# SparkFun_DataLogger_IoT.net
KiCad netlist of a schematic drawn in EAGLE
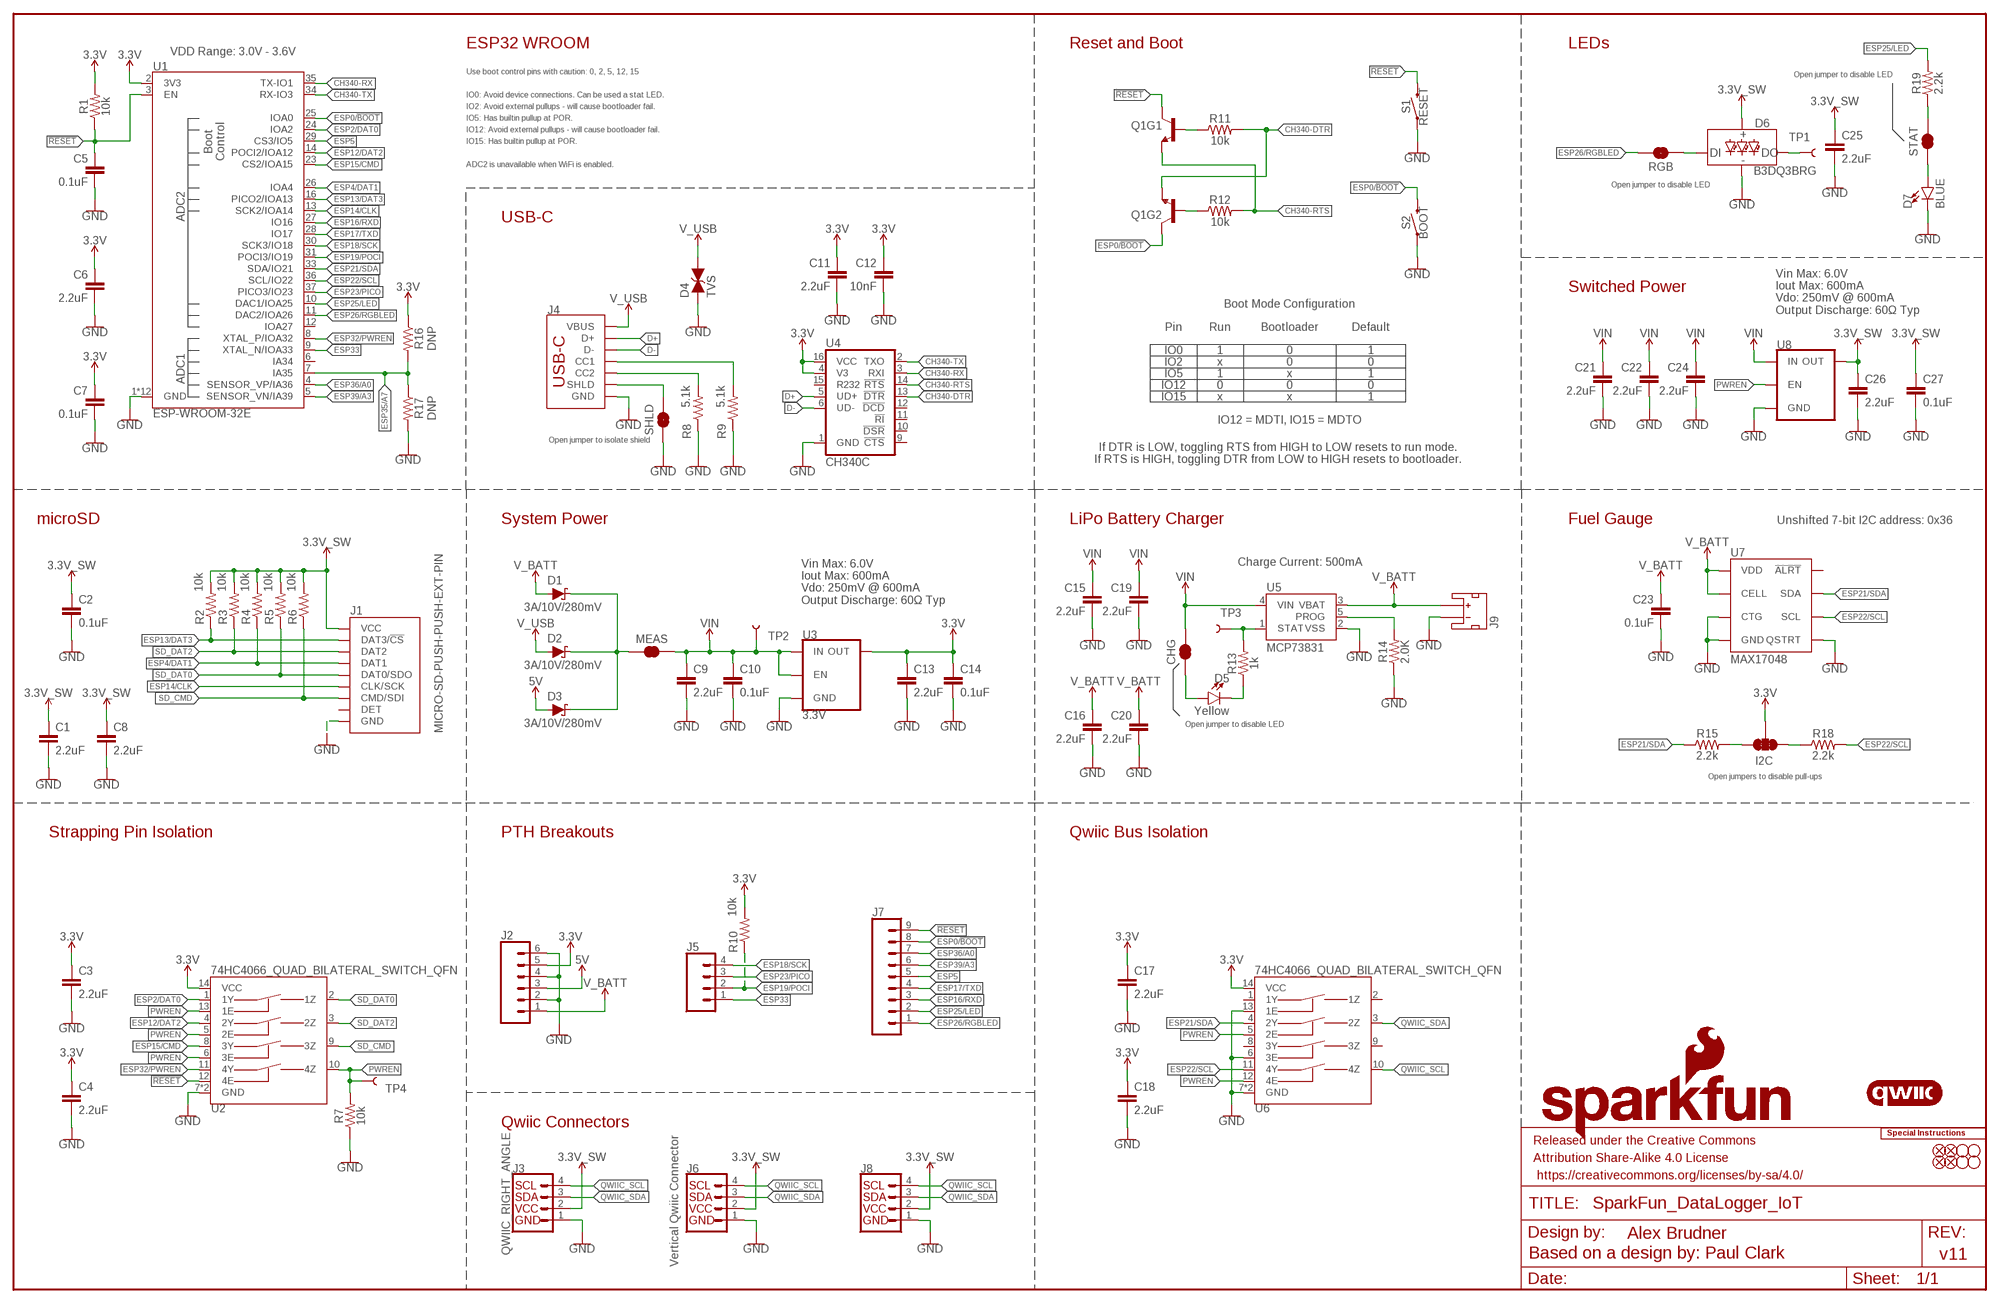
[diagram p0: schematic, sheet 1]

(export (version "E")
  (design (tool "Eeschema 10.0.6"))
  (components
    (comp (ref "C1")
      (value "2.2uF")
      (footprint "eagle-import:0402-TIGHT")
      (libsource (lib "eagle-import") (part "2.2UF-0402_TIGHT-10V-10%-X5R"))
    )
    (comp (ref "C2")
      (value "0.1uF")
      (footprint "eagle-import:0402-TIGHT")
      (libsource (lib "eagle-import") (part "0.1UF-0402T-6.3V-10%-X7R"))
    )
    (comp (ref "C3")
      (value "2.2uF")
      (footprint "eagle-import:0402-TIGHT")
      (libsource (lib "eagle-import") (part "2.2UF-0402_TIGHT-10V-10%-X5R"))
    )
    (comp (ref "C4")
      (value "2.2uF")
      (footprint "eagle-import:0402-TIGHT")
      (libsource (lib "eagle-import") (part "2.2UF-0402_TIGHT-10V-10%-X5R"))
    )
    (comp (ref "C5")
      (value "0.1uF")
      (footprint "eagle-import:0402-TIGHT")
      (libsource (lib "eagle-import") (part "0.1UF-0402T-6.3V-10%-X7R"))
    )
    (comp (ref "C6")
      (value "2.2uF")
      (footprint "eagle-import:0402-TIGHT")
      (libsource (lib "eagle-import") (part "2.2UF-0402_TIGHT-10V-10%-X5R"))
    )
    (comp (ref "C7")
      (value "0.1uF")
      (footprint "eagle-import:0402-TIGHT")
      (libsource (lib "eagle-import") (part "0.1UF-0402T-6.3V-10%-X7R"))
    )
    (comp (ref "C8")
      (value "2.2uF")
      (footprint "eagle-import:0402-TIGHT")
      (libsource (lib "eagle-import") (part "2.2UF-0402_TIGHT-10V-10%-X5R"))
    )
    (comp (ref "C9")
      (value "2.2uF")
      (footprint "eagle-import:0402-TIGHT")
      (libsource (lib "eagle-import") (part "2.2UF-0402_TIGHT-10V-10%-X5R"))
    )
    (comp (ref "C10")
      (value "0.1uF")
      (footprint "eagle-import:0402-TIGHT")
      (libsource (lib "eagle-import") (part "0.1UF-0402T-6.3V-10%-X7R"))
    )
    (comp (ref "C11")
      (value "2.2uF")
      (footprint "eagle-import:0402-TIGHT")
      (libsource (lib "eagle-import") (part "2.2UF-0402_TIGHT-10V-10%-X5R"))
    )
    (comp (ref "C12")
      (value "10nF")
      (footprint "eagle-import:0402-TIGHT")
      (libsource (lib "eagle-import") (part "10NF-0402T-25V-10%-X7R-WE"))
    )
    (comp (ref "C13")
      (value "2.2uF")
      (footprint "eagle-import:0402-TIGHT")
      (libsource (lib "eagle-import") (part "2.2UF-0402_TIGHT-10V-10%-X5R"))
    )
    (comp (ref "C14")
      (value "0.1uF")
      (footprint "eagle-import:0402-TIGHT")
      (libsource (lib "eagle-import") (part "0.1UF-0402T-6.3V-10%-X7R"))
    )
    (comp (ref "C15")
      (value "2.2uF")
      (footprint "eagle-import:0402-TIGHT")
      (libsource (lib "eagle-import") (part "2.2UF-0402_TIGHT-10V-10%-X5R"))
    )
    (comp (ref "C16")
      (value "2.2uF")
      (footprint "eagle-import:0402-TIGHT")
      (libsource (lib "eagle-import") (part "2.2UF-0402_TIGHT-10V-10%-X5R"))
    )
    (comp (ref "C17")
      (value "2.2uF")
      (footprint "eagle-import:0402-TIGHT")
      (libsource (lib "eagle-import") (part "2.2UF-0402_TIGHT-10V-10%-X5R"))
    )
    (comp (ref "C18")
      (value "2.2uF")
      (footprint "eagle-import:0402-TIGHT")
      (libsource (lib "eagle-import") (part "2.2UF-0402_TIGHT-10V-10%-X5R"))
    )
    (comp (ref "C19")
      (value "2.2uF")
      (footprint "eagle-import:0402-TIGHT")
      (libsource (lib "eagle-import") (part "2.2UF-0402_TIGHT-10V-10%-X5R"))
    )
    (comp (ref "C20")
      (value "2.2uF")
      (footprint "eagle-import:0402-TIGHT")
      (libsource (lib "eagle-import") (part "2.2UF-0402_TIGHT-10V-10%-X5R"))
    )
    (comp (ref "C21")
      (value "2.2uF")
      (footprint "eagle-import:0402-TIGHT")
      (libsource (lib "eagle-import") (part "2.2UF-0402_TIGHT-10V-10%-X5R"))
    )
    (comp (ref "C22")
      (value "2.2uF")
      (footprint "eagle-import:0402-TIGHT")
      (libsource (lib "eagle-import") (part "2.2UF-0402_TIGHT-10V-10%-X5R"))
    )
    (comp (ref "C23")
      (value "0.1uF")
      (footprint "eagle-import:0402-TIGHT")
      (libsource (lib "eagle-import") (part "0.1UF-0402T-6.3V-10%-X7R"))
    )
    (comp (ref "C24")
      (value "2.2uF")
      (footprint "eagle-import:0402-TIGHT")
      (libsource (lib "eagle-import") (part "2.2UF-0402_TIGHT-10V-10%-X5R"))
    )
    (comp (ref "C25")
      (value "2.2uF")
      (footprint "eagle-import:0402-TIGHT")
      (libsource (lib "eagle-import") (part "2.2UF-0402_TIGHT-10V-10%-X5R"))
    )
    (comp (ref "C26")
      (value "2.2uF")
      (footprint "eagle-import:0402-TIGHT")
      (libsource (lib "eagle-import") (part "2.2UF-0402_TIGHT-10V-10%-X5R"))
    )
    (comp (ref "C27")
      (value "0.1uF")
      (footprint "eagle-import:0402-TIGHT")
      (libsource (lib "eagle-import") (part "0.1UF-0402T-6.3V-10%-X7R"))
    )
    (comp (ref "CHG")
      (value "JUMPER-SMT_2_NC_TRACE_SILK")
      (footprint "eagle-import:SMT-JUMPER_2_NC_TRACE_SILK")
      (libsource (lib "eagle-import") (part "JUMPER-SMT_2_NC_TRACE_SILK"))
    )
    (comp (ref "D1")
      (value "3A/10V/280mV")
      (footprint "eagle-import:SOD-323")
      (libsource (lib "eagle-import") (part "DIODE-SCHOTTKY-BAT60A"))
    )
    (comp (ref "D2")
      (value "3A/10V/280mV")
      (footprint "eagle-import:SOD-323")
      (libsource (lib "eagle-import") (part "DIODE-SCHOTTKY-BAT60A"))
    )
    (comp (ref "D3")
      (value "3A/10V/280mV")
      (footprint "eagle-import:SOD-323")
      (libsource (lib "eagle-import") (part "DIODE-SCHOTTKY-BAT60A"))
    )
    (comp (ref "D4")
      (value "TVS")
      (footprint "eagle-import:0603")
      (libsource (lib "eagle-import") (part "DIODE_TVS"))
    )
    (comp (ref "D5")
      (value "Yellow")
      (footprint "eagle-import:LED-0603")
      (libsource (lib "eagle-import") (part "LED-YELLOW0603"))
    )
    (comp (ref "D6")
      (value "B3DQ3BRG")
      (footprint "eagle-import:B3DQ3BRG")
      (libsource (lib "eagle-import") (part "B3DQ3BRG"))
    )
    (comp (ref "D7")
      (value "BLUE")
      (footprint "eagle-import:LED-0603")
      (libsource (lib "eagle-import") (part "LED-BLUE0603"))
    )
    (comp (ref "FD1")
      (value "FIDUCIAL1X2")
      (footprint "eagle-import:FIDUCIAL-1X2")
      (libsource (lib "eagle-import") (part "FIDUCIAL1X2"))
    )
    (comp (ref "FD2")
      (value "FIDUCIAL1X2")
      (footprint "eagle-import:FIDUCIAL-1X2")
      (libsource (lib "eagle-import") (part "FIDUCIAL1X2"))
    )
    (comp (ref "FD3")
      (value "FIDUCIAL1X2")
      (footprint "eagle-import:FIDUCIAL-1X2")
      (libsource (lib "eagle-import") (part "FIDUCIAL1X2"))
    )
    (comp (ref "FD4")
      (value "FIDUCIAL1X2")
      (footprint "eagle-import:FIDUCIAL-1X2")
      (libsource (lib "eagle-import") (part "FIDUCIAL1X2"))
    )
    (comp (ref "FRAME1")
      (value "FRAME-LEDGER")
      (footprint "eagle-import:CREATIVE_COMMONS")
      (fields (field (name "DESIGNER") "Alex Brudner") (field (name "REV") "v11"))
      (libsource (lib "eagle-import") (part "FRAME-LEDGER"))
    )
    (comp (ref "H1")
      (value "STAND-OFFTIGHT")
      (footprint "eagle-import:STAND-OFF-TIGHT")
      (libsource (lib "eagle-import") (part "STAND-OFFTIGHT"))
    )
    (comp (ref "H2")
      (value "STAND-OFFTIGHT")
      (footprint "eagle-import:STAND-OFF-TIGHT")
      (libsource (lib "eagle-import") (part "STAND-OFFTIGHT"))
    )
    (comp (ref "H3")
      (value "STAND-OFFTIGHT")
      (footprint "eagle-import:STAND-OFF-TIGHT")
      (libsource (lib "eagle-import") (part "STAND-OFFTIGHT"))
    )
    (comp (ref "H4")
      (value "STAND-OFFTIGHT")
      (footprint "eagle-import:STAND-OFF-TIGHT")
      (libsource (lib "eagle-import") (part "STAND-OFFTIGHT"))
    )
    (comp (ref "I2C")
      (value "JUMPER-SMT_3_2-NC_TRACE_SILK")
      (footprint "eagle-import:SMT-JUMPER_3_2-NC_TRACE_SILK")
      (libsource (lib "eagle-import") (part "JUMPER-SMT_3_2-NC_TRACE_SILK"))
    )
    (comp (ref "J1")
      (value "MICRO-SD-PUSH-PUSH-EXT-PIN")
      (footprint "eagle-import:MICROSD-EXTERNALPIN")
      (libsource (lib "eagle-import") (part "MICRO-SD-PUSH-PUSH-EXT-PIN"))
    )
    (comp (ref "J2")
      (value "CONN_06NO_SILK_NO_POP")
      (footprint "eagle-import:1X06_NO_SILK")
      (libsource (lib "eagle-import") (part "CONN_06NO_SILK_NO_POP"))
    )
    (comp (ref "J3")
      (value "QWIIC_RIGHT_ANGLE")
      (footprint "eagle-import:JST04_1MM_RA")
      (libsource (lib "eagle-import") (part "QWIIC_CONNECTORJS-1MM"))
    )
    (comp (ref "J4")
      (value "USB_C_4-LAYER_PADS")
      (footprint "eagle-import:USB-C-16P_4LAYER-PADS")
      (libsource (lib "eagle-import") (part "USB_C_4-LAYER_PADS"))
    )
    (comp (ref "J5")
      (value "CONN_041X04_NO_SILK_NO_POP")
      (footprint "eagle-import:1X04_NO_SILK")
      (libsource (lib "eagle-import") (part "CONN_041X04_NO_SILK_NO_POP"))
    )
    (comp (ref "J6")
      (value "Vertical Qwiic Connector")
      (footprint "eagle-import:JST04_1MM_VERT")
      (libsource (lib "eagle-import") (part "QWIIC_CONNECTOR"))
    )
    (comp (ref "J7")
      (value "CONN_09NO_SILK")
      (footprint "eagle-import:1X09_NO_SILK")
      (libsource (lib "eagle-import") (part "CONN_09NO_SILK"))
    )
    (comp (ref "J8")
      (value "I2C_STANDARD_NO_SILK")
      (footprint "eagle-import:1X04_NO_SILK")
      (libsource (lib "eagle-import") (part "I2C_STANDARD_NO_SILK"))
    )
    (comp (ref "J9")
      (value "JST_2MM_MALE")
      (footprint "eagle-import:JST-2-SMD")
      (libsource (lib "eagle-import") (part "JST_2MM_MALE"))
    )
    (comp (ref "LOGO1")
      (value "SFE_LOGO_NAME.2_INCH")
      (footprint "eagle-import:SFE_LOGO_NAME_.2")
      (libsource (lib "eagle-import") (part "SFE_LOGO_NAME.2_INCH"))
    )
    (comp (ref "LOGO2")
      (value "SFE_LOGO_FLAME.2_INCH")
      (footprint "eagle-import:SFE_LOGO_FLAME_.2")
      (libsource (lib "eagle-import") (part "SFE_LOGO_FLAME.2_INCH"))
    )
    (comp (ref "LOGO3")
      (value "SPECIAL_INSTRUCTIONS-ORDERING")
      (footprint "eagle-import:ORDERING_INSTRUCTIONS")
      (libsource (lib "eagle-import") (part "SPECIAL_INSTRUCTIONS-ORDERING"))
    )
    (comp (ref "LOGO4")
      (value "QWIIC_LOGO_6MM")
      (footprint "eagle-import:QWIIC_6MM")
      (libsource (lib "eagle-import") (part "QWIIC_LOGO_6MM"))
    )
    (comp (ref "MEAS")
      (value "JUMPER-COMBO_2_NC_TRACE")
      (footprint "eagle-import:COMBO-JUMPER_2_NC_TRACE")
      (libsource (lib "eagle-import") (part "JUMPER-COMBO_2_NC_TRACE"))
    )
    (comp (ref "Q1")
      (value "TRANS_NPN_DUAL-MBT3904DW1T1")
      (footprint "eagle-import:SC70-6")
      (libsource (lib "eagle-import") (part "TRANS_NPN_DUAL-MBT3904DW1T1"))
    )
    (comp (ref "R1")
      (value "10k")
      (footprint "eagle-import:0402-TIGHT")
      (libsource (lib "eagle-import") (part "10KOHM-0402T-1/16W-1%"))
    )
    (comp (ref "R2")
      (value "10k")
      (footprint "eagle-import:0402-TIGHT")
      (libsource (lib "eagle-import") (part "10KOHM-0402T-1/16W-1%"))
    )
    (comp (ref "R3")
      (value "10k")
      (footprint "eagle-import:0402-TIGHT")
      (libsource (lib "eagle-import") (part "10KOHM-0402T-1/16W-1%"))
    )
    (comp (ref "R4")
      (value "10k")
      (footprint "eagle-import:0402-TIGHT")
      (libsource (lib "eagle-import") (part "10KOHM-0402T-1/16W-1%"))
    )
    (comp (ref "R5")
      (value "10k")
      (footprint "eagle-import:0402-TIGHT")
      (libsource (lib "eagle-import") (part "10KOHM-0402T-1/16W-1%"))
    )
    (comp (ref "R6")
      (value "10k")
      (footprint "eagle-import:0402-TIGHT")
      (libsource (lib "eagle-import") (part "10KOHM-0402T-1/16W-1%"))
    )
    (comp (ref "R7")
      (value "10k")
      (footprint "eagle-import:0402-TIGHT")
      (libsource (lib "eagle-import") (part "10KOHM-0402T-1/16W-1%"))
    )
    (comp (ref "R8")
      (value "5.1k")
      (footprint "eagle-import:0402-TIGHT")
      (libsource (lib "eagle-import") (part "5.1KOHM-0402T-1/16W-1%"))
    )
    (comp (ref "R9")
      (value "5.1k")
      (footprint "eagle-import:0402-TIGHT")
      (libsource (lib "eagle-import") (part "5.1KOHM-0402T-1/16W-1%"))
    )
    (comp (ref "R10")
      (value "10k")
      (footprint "eagle-import:0402-TIGHT")
      (libsource (lib "eagle-import") (part "10KOHM-0402T-1/16W-1%"))
    )
    (comp (ref "R11")
      (value "10k")
      (footprint "eagle-import:0402-TIGHT")
      (libsource (lib "eagle-import") (part "10KOHM-0402T-1/16W-1%"))
    )
    (comp (ref "R12")
      (value "10k")
      (footprint "eagle-import:0402-TIGHT")
      (libsource (lib "eagle-import") (part "10KOHM-0402T-1/16W-1%"))
    )
    (comp (ref "R13")
      (value "1k")
      (footprint "eagle-import:0402-TIGHT")
      (libsource (lib "eagle-import") (part "1KOHM-0402T-1/16W-1%"))
    )
    (comp (ref "R14")
      (value "2.0K")
      (footprint "eagle-import:0402-TIGHT")
      (libsource (lib "eagle-import") (part "2.0KOHM-0402T-1/16W-1%"))
    )
    (comp (ref "R15")
      (value "2.2k")
      (footprint "eagle-import:0402-TIGHT")
      (libsource (lib "eagle-import") (part "2.2KOHM-0402T-1/16W-1%"))
    )
    (comp (ref "R16")
      (value "DNP")
      (footprint "eagle-import:0402-TIGHT_NO_CREAM")
      (libsource (lib "eagle-import") (part "DNP-0402T_NO_CREAM"))
    )
    (comp (ref "R17")
      (value "DNP")
      (footprint "eagle-import:0402-TIGHT_NO_CREAM")
      (libsource (lib "eagle-import") (part "DNP-0402T_NO_CREAM"))
    )
    (comp (ref "R18")
      (value "2.2k")
      (footprint "eagle-import:0402-TIGHT")
      (libsource (lib "eagle-import") (part "2.2KOHM-0402T-1/16W-1%"))
    )
    (comp (ref "R19")
      (value "2.2k")
      (footprint "eagle-import:0402-TIGHT")
      (libsource (lib "eagle-import") (part "2.2KOHM-0402T-1/16W-1%"))
    )
    (comp (ref "RGB")
      (value "JUMPER-SMT_2_NC_TRACE_SILK")
      (footprint "eagle-import:SMT-JUMPER_2_NC_TRACE_SILK")
      (libsource (lib "eagle-import") (part "JUMPER-SMT_2_NC_TRACE_SILK"))
    )
    (comp (ref "S1")
      (value "RESET")
      (footprint "eagle-import:TACTILE_SWITCH_SMD_RIGHT_ANGLE")
      (libsource (lib "eagle-import") (part "MOMENTARY-SWITCH-SPST-SMD-RIGHT-ANGLE"))
    )
    (comp (ref "S2")
      (value "BOOT")
      (footprint "eagle-import:TACTILE_SWITCH_SMD_RIGHT_ANGLE")
      (libsource (lib "eagle-import") (part "MOMENTARY-SWITCH-SPST-SMD-RIGHT-ANGLE"))
    )
    (comp (ref "SHLD")
      (value "JUMPER-SMT_2_NC_TRACE_SILK")
      (footprint "eagle-import:SMT-JUMPER_2_NC_TRACE_SILK")
      (libsource (lib "eagle-import") (part "JUMPER-SMT_2_NC_TRACE_SILK"))
    )
    (comp (ref "STAT")
      (value "JUMPER-SMT_2_NC_TRACE_SILK")
      (footprint "eagle-import:SMT-JUMPER_2_NC_TRACE_SILK")
      (libsource (lib "eagle-import") (part "JUMPER-SMT_2_NC_TRACE_SILK"))
    )
    (comp (ref "TP1")
      (value "TEST-POINT3X5")
      (footprint "eagle-import:PAD.03X.05")
      (libsource (lib "eagle-import") (part "TEST-POINT3X5"))
    )
    (comp (ref "TP2")
      (value "TEST-POINT3X5")
      (footprint "eagle-import:PAD.03X.05")
      (libsource (lib "eagle-import") (part "TEST-POINT3X5"))
    )
    (comp (ref "TP3")
      (value "TEST-POINT3X5")
      (footprint "eagle-import:PAD.03X.05")
      (libsource (lib "eagle-import") (part "TEST-POINT3X5"))
    )
    (comp (ref "TP4")
      (value "TEST-POINT3X5")
      (footprint "eagle-import:PAD.03X.05")
      (libsource (lib "eagle-import") (part "TEST-POINT3X5"))
    )
    (comp (ref "U1")
      (value "ESP-WROOM-32E")
      (footprint "eagle-import:ESP-WROOM-32D-NARROW")
      (libsource (lib "eagle-import") (part "ESP-WROOM-3232D-NARROW"))
    )
    (comp (ref "U2")
      (value "74HC4066_QUAD_BILATERAL_SWITCH_QFN")
      (footprint "eagle-import:14-QFN")
      (libsource (lib "eagle-import") (part "74HC4066_QUAD_BILATERAL_SWITCH_QFN"))
    )
    (comp (ref "U3")
      (value "3.3V")
      (footprint "eagle-import:SOT23-5")
      (libsource (lib "eagle-import") (part "V_REG_AP2112K-3.3V"))
    )
    (comp (ref "U4")
      (value "CH340C")
      (footprint "eagle-import:SO016")
      (libsource (lib "eagle-import") (part "CH340C"))
    )
    (comp (ref "U5")
      (value "MCP73831")
      (footprint "eagle-import:SOT23-5")
      (libsource (lib "eagle-import") (part "MCP73831"))
    )
    (comp (ref "U6")
      (value "74HC4066_QUAD_BILATERAL_SWITCH_QFN")
      (footprint "eagle-import:14-QFN")
      (libsource (lib "eagle-import") (part "74HC4066_QUAD_BILATERAL_SWITCH_QFN"))
    )
    (comp (ref "U7")
      (value "MAX17048")
      (footprint "eagle-import:DFN-8")
      (libsource (lib "eagle-import") (part "MAX17048DFN8"))
    )
    (comp (ref "U8")
      (value "3.3V")
      (footprint "eagle-import:SOT23-5")
      (libsource (lib "eagle-import") (part "V_REG_AP2112K-3.3V"))
    )
  )
  (nets
    (net (code "1") (name "/ESP0{slash}~{BOOT}") (class "Default")
      (node (ref "J7") (pin "8") (pinfunction "8_8") (pintype "passive"))
      (node (ref "Q1") (pin "6") (pinfunction "C_6") (pintype "passive"))
      (node (ref "S2") (pin "2") (pinfunction "2_2") (pintype "passive"))
      (node (ref "U1") (pin "25") (pinfunction "IOA0_25") (pintype "bidirectional"))
    )
    (net (code "2") (name "/~{RESET}") (class "Default")
      (node (ref "C5") (pin "1") (pinfunction "1_1") (pintype "passive"))
      (node (ref "J7") (pin "9") (pinfunction "9_9") (pintype "passive"))
      (node (ref "Q1") (pin "3") (pinfunction "C_3") (pintype "passive"))
      (node (ref "R1") (pin "1") (pinfunction "1_1") (pintype "passive"))
      (node (ref "S1") (pin "2") (pinfunction "2_2") (pintype "passive"))
      (node (ref "U1") (pin "3") (pinfunction "EN_3") (pintype "bidirectional"))
      (node (ref "U2") (pin "12") (pinfunction "4E_12") (pintype "bidirectional"))
    )
    (net (code "3") (name "3.3V") (class "Default")
      (node (ref "C11") (pin "1") (pinfunction "1_1") (pintype "passive"))
      (node (ref "C12") (pin "1") (pinfunction "1_1") (pintype "passive"))
      (node (ref "C13") (pin "1") (pinfunction "1_1") (pintype "passive"))
      (node (ref "C14") (pin "1") (pinfunction "1_1") (pintype "passive"))
      (node (ref "C17") (pin "1") (pinfunction "1_1") (pintype "passive"))
      (node (ref "C18") (pin "1") (pinfunction "1_1") (pintype "passive"))
      (node (ref "C3") (pin "1") (pinfunction "1_1") (pintype "passive"))
      (node (ref "C4") (pin "1") (pinfunction "1_1") (pintype "passive"))
      (node (ref "C6") (pin "1") (pinfunction "1_1") (pintype "passive"))
      (node (ref "C7") (pin "1") (pinfunction "1_1") (pintype "passive"))
      (node (ref "I2C") (pin "2") (pinfunction "2_2") (pintype "passive"))
      (node (ref "J2") (pin "5") (pinfunction "5_5") (pintype "passive"))
      (node (ref "R1") (pin "2") (pinfunction "2_2") (pintype "passive"))
      (node (ref "R10") (pin "2") (pinfunction "2_2") (pintype "passive"))
      (node (ref "R16") (pin "1") (pinfunction "1_1") (pintype "passive"))
      (node (ref "U1") (pin "2") (pinfunction "3V3_2") (pintype "bidirectional"))
      (node (ref "U2") (pin "14") (pinfunction "VCC_14") (pintype "bidirectional"))
      (node (ref "U3") (pin "5") (pinfunction "OUT_5") (pintype "passive"))
      (node (ref "U4") (pin "16") (pinfunction "VCC_16") (pintype "bidirectional"))
      (node (ref "U4") (pin "4") (pinfunction "V3_4") (pintype "bidirectional"))
      (node (ref "U6") (pin "14") (pinfunction "VCC_14") (pintype "bidirectional"))
    )
    (net (code "4") (name "3.3V_SW") (class "Default")
      (node (ref "C1") (pin "1") (pinfunction "1_1") (pintype "passive"))
      (node (ref "C2") (pin "1") (pinfunction "1_1") (pintype "passive"))
      (node (ref "C25") (pin "1") (pinfunction "1_1") (pintype "passive"))
      (node (ref "C26") (pin "1") (pinfunction "1_1") (pintype "passive"))
      (node (ref "C27") (pin "1") (pinfunction "1_1") (pintype "passive"))
      (node (ref "C8") (pin "1") (pinfunction "1_1") (pintype "passive"))
      (node (ref "D6") (pin "2") (pinfunction "VCC_2") (pintype "bidirectional"))
      (node (ref "J1") (pin "4") (pinfunction "VCC_4") (pintype "bidirectional"))
      (node (ref "J3") (pin "2") (pinfunction "2_2") (pintype "power_in"))
      (node (ref "J6") (pin "2") (pinfunction "2_2") (pintype "power_in"))
      (node (ref "J8") (pin "2") (pinfunction "2_2") (pintype "power_in"))
      (node (ref "R2") (pin "2") (pinfunction "2_2") (pintype "passive"))
      (node (ref "R3") (pin "2") (pinfunction "2_2") (pintype "passive"))
      (node (ref "R4") (pin "2") (pinfunction "2_2") (pintype "passive"))
      (node (ref "R5") (pin "2") (pinfunction "2_2") (pintype "passive"))
      (node (ref "R6") (pin "2") (pinfunction "2_2") (pintype "passive"))
      (node (ref "U8") (pin "5") (pinfunction "OUT_5") (pintype "passive"))
    )
    (net (code "5") (name "5V") (class "Default")
      (node (ref "D3") (pin "A") (pinfunction "A_A") (pintype "passive"))
      (node (ref "J2") (pin "3") (pinfunction "3_3") (pintype "passive"))
    )
    (net (code "6") (name "CH340-DTR") (class "Default")
      (node (ref "Q1") (pin "1") (pinfunction "E_1") (pintype "passive"))
      (node (ref "R11") (pin "2") (pinfunction "2_2") (pintype "passive"))
      (node (ref "U4") (pin "13") (pinfunction "~{DTR}_13") (pintype "bidirectional"))
    )
    (net (code "7") (name "CH340-RTS") (class "Default")
      (node (ref "Q1") (pin "4") (pinfunction "E_4") (pintype "passive"))
      (node (ref "R12") (pin "2") (pinfunction "2_2") (pintype "passive"))
      (node (ref "U4") (pin "14") (pinfunction "~{RTS}_14") (pintype "bidirectional"))
    )
    (net (code "8") (name "CH340-RX") (class "Default")
      (node (ref "U1") (pin "35") (pinfunction "TX-IO1_35") (pintype "bidirectional"))
      (node (ref "U4") (pin "3") (pinfunction "RXI_3") (pintype "bidirectional"))
    )
    (net (code "9") (name "CH340-TX") (class "Default")
      (node (ref "U1") (pin "34") (pinfunction "RX-IO3_34") (pintype "bidirectional"))
      (node (ref "U4") (pin "2") (pinfunction "TXO_2") (pintype "bidirectional"))
    )
    (net (code "10") (name "D+") (class "Default")
      (node (ref "J4") (pin "A6") (pinfunction "D+_A6") (pintype "bidirectional"))
      (node (ref "J4") (pin "B6") (pinfunction "D+_B6") (pintype "bidirectional"))
      (node (ref "U4") (pin "5") (pinfunction "UD+_5") (pintype "bidirectional"))
    )
    (net (code "11") (name "D-") (class "Default")
      (node (ref "J4") (pin "A7") (pinfunction "D-_A7") (pintype "bidirectional"))
      (node (ref "J4") (pin "B7") (pinfunction "D-_B7") (pintype "bidirectional"))
      (node (ref "U4") (pin "6") (pinfunction "UD-_6") (pintype "bidirectional"))
    )
    (net (code "12") (name "ESP2{slash}DAT0") (class "Default")
      (node (ref "U1") (pin "24") (pinfunction "IOA2_24") (pintype "bidirectional"))
      (node (ref "U2") (pin "1") (pinfunction "1Y_1") (pintype "bidirectional"))
    )
    (net (code "13") (name "ESP4{slash}DAT1") (class "Default")
      (node (ref "J1") (pin "8") (pinfunction "DAT1_8") (pintype "bidirectional"))
      (node (ref "R4") (pin "1") (pinfunction "1_1") (pintype "passive"))
      (node (ref "U1") (pin "26") (pinfunction "IOA4_26") (pintype "bidirectional"))
    )
    (net (code "14") (name "ESP5") (class "Default")
      (node (ref "J7") (pin "5") (pinfunction "5_5") (pintype "passive"))
      (node (ref "U1") (pin "29") (pinfunction "CS3/IO5_29") (pintype "bidirectional"))
    )
    (net (code "15") (name "ESP12{slash}DAT2") (class "Default")
      (node (ref "U1") (pin "14") (pinfunction "POCI2/IOA12_14") (pintype "bidirectional"))
      (node (ref "U2") (pin "4") (pinfunction "2Y_4") (pintype "bidirectional"))
    )
    (net (code "16") (name "ESP13{slash}DAT3") (class "Default")
      (node (ref "J1") (pin "2") (pinfunction "DAT3/~{CS}_2") (pintype "bidirectional"))
      (node (ref "R2") (pin "1") (pinfunction "1_1") (pintype "passive"))
      (node (ref "U1") (pin "16") (pinfunction "PICO2/IOA13_16") (pintype "bidirectional"))
    )
    (net (code "17") (name "ESP14{slash}CLK") (class "Default")
      (node (ref "J1") (pin "5") (pinfunction "CLK/SCK_5") (pintype "bidirectional"))
      (node (ref "U1") (pin "13") (pinfunction "SCK2/IOA14_13") (pintype "bidirectional"))
    )
    (net (code "18") (name "ESP15{slash}CMD") (class "Default")
      (node (ref "U1") (pin "23") (pinfunction "CS2/IOA15_23") (pintype "bidirectional"))
      (node (ref "U2") (pin "8") (pinfunction "3Y_8") (pintype "bidirectional"))
    )
    (net (code "19") (name "ESP16{slash}RXD") (class "Default")
      (node (ref "J7") (pin "3") (pinfunction "3_3") (pintype "passive"))
      (node (ref "U1") (pin "27") (pinfunction "IO16_27") (pintype "bidirectional"))
    )
    (net (code "20") (name "ESP17{slash}TXD") (class "Default")
      (node (ref "J7") (pin "4") (pinfunction "4_4") (pintype "passive"))
      (node (ref "U1") (pin "28") (pinfunction "IO17_28") (pintype "bidirectional"))
    )
    (net (code "21") (name "ESP18{slash}SCK") (class "Default")
      (node (ref "J5") (pin "4") (pinfunction "4_4") (pintype "passive"))
      (node (ref "U1") (pin "30") (pinfunction "SCK3/IO18_30") (pintype "bidirectional"))
    )
    (net (code "22") (name "ESP19{slash}POCI") (class "Default")
      (node (ref "J5") (pin "2") (pinfunction "2_2") (pintype "passive"))
      (node (ref "R10") (pin "1") (pinfunction "1_1") (pintype "passive"))
      (node (ref "U1") (pin "31") (pinfunction "POCI3/IO19_31") (pintype "bidirectional"))
    )
    (net (code "23") (name "ESP21{slash}SDA") (class "Default")
      (node (ref "R15") (pin "1") (pinfunction "1_1") (pintype "passive"))
      (node (ref "U1") (pin "33") (pinfunction "SDA/IO21_33") (pintype "bidirectional"))
      (node (ref "U6") (pin "4") (pinfunction "2Y_4") (pintype "bidirectional"))
      (node (ref "U7") (pin "8") (pinfunction "SDA_8") (pintype "input"))
    )
    (net (code "24") (name "ESP22{slash}SCL") (class "Default")
      (node (ref "R18") (pin "2") (pinfunction "2_2") (pintype "passive"))
      (node (ref "U1") (pin "36") (pinfunction "SCL/IO22_36") (pintype "bidirectional"))
      (node (ref "U6") (pin "11") (pinfunction "4Y_11") (pintype "bidirectional"))
      (node (ref "U7") (pin "7") (pinfunction "SCL_7") (pintype "output"))
    )
    (net (code "25") (name "ESP23{slash}PICO") (class "Default")
      (node (ref "J5") (pin "3") (pinfunction "3_3") (pintype "passive"))
      (node (ref "U1") (pin "37") (pinfunction "PICO3/IO23_37") (pintype "bidirectional"))
    )
    (net (code "26") (name "ESP25{slash}LED") (class "Default")
      (node (ref "J7") (pin "2") (pinfunction "2_2") (pintype "passive"))
      (node (ref "R19") (pin "2") (pinfunction "2_2") (pintype "passive"))
      (node (ref "U1") (pin "10") (pinfunction "DAC1/IOA25_10") (pintype "bidirectional"))
    )
    (net (code "27") (name "ESP26{slash}RGBLED") (class "Default")
      (node (ref "J7") (pin "1") (pinfunction "1_1") (pintype "passive"))
      (node (ref "RGB") (pin "2") (pinfunction "2_2") (pintype "passive"))
      (node (ref "U1") (pin "11") (pinfunction "DAC2/IOA26_11") (pintype "bidirectional"))
    )
    (net (code "28") (name "ESP32{slash}PWREN") (class "Default")
      (node (ref "U1") (pin "8") (pinfunction "XTAL_P/IOA32_8") (pintype "bidirectional"))
      (node (ref "U2") (pin "11") (pinfunction "4Y_11") (pintype "bidirectional"))
    )
    (net (code "29") (name "ESP33") (class "Default")
      (node (ref "J5") (pin "1") (pinfunction "1_1") (pintype "passive"))
      (node (ref "U1") (pin "9") (pinfunction "XTAL_N/IOA33_9") (pintype "bidirectional"))
    )
    (net (code "30") (name "ESP35{slash}A7") (class "Default")
      (node (ref "R16") (pin "2") (pinfunction "2_2") (pintype "passive"))
      (node (ref "R17") (pin "1") (pinfunction "1_1") (pintype "passive"))
      (node (ref "U1") (pin "7") (pinfunction "IA35_7") (pintype "bidirectional"))
    )
    (net (code "31") (name "ESP36{slash}A0") (class "Default")
      (node (ref "J7") (pin "7") (pinfunction "7_7") (pintype "passive"))
      (node (ref "U1") (pin "4") (pinfunction "SENSOR_VP/IA36_4") (pintype "bidirectional"))
    )
    (net (code "32") (name "ESP39{slash}A3") (class "Default")
      (node (ref "J7") (pin "6") (pinfunction "6_6") (pintype "passive"))
      (node (ref "U1") (pin "5") (pinfunction "SENSOR_VN/IA39_5") (pintype "bidirectional"))
    )
    (net (code "33") (name "GND") (class "Default")
      (node (ref "C1") (pin "2") (pinfunction "2_2") (pintype "passive"))
      (node (ref "C10") (pin "2") (pinfunction "2_2") (pintype "passive"))
      (node (ref "C11") (pin "2") (pinfunction "2_2") (pintype "passive"))
      (node (ref "C12") (pin "2") (pinfunction "2_2") (pintype "passive"))
      (node (ref "C13") (pin "2") (pinfunction "2_2") (pintype "passive"))
      (node (ref "C14") (pin "2") (pinfunction "2_2") (pintype "passive"))
      (node (ref "C15") (pin "2") (pinfunction "2_2") (pintype "passive"))
      (node (ref "C16") (pin "2") (pinfunction "2_2") (pintype "passive"))
      (node (ref "C17") (pin "2") (pinfunction "2_2") (pintype "passive"))
      (node (ref "C18") (pin "2") (pinfunction "2_2") (pintype "passive"))
      (node (ref "C19") (pin "2") (pinfunction "2_2") (pintype "passive"))
      (node (ref "C2") (pin "2") (pinfunction "2_2") (pintype "passive"))
      (node (ref "C20") (pin "2") (pinfunction "2_2") (pintype "passive"))
      (node (ref "C21") (pin "2") (pinfunction "2_2") (pintype "passive"))
      (node (ref "C22") (pin "2") (pinfunction "2_2") (pintype "passive"))
      (node (ref "C23") (pin "2") (pinfunction "2_2") (pintype "passive"))
      (node (ref "C24") (pin "2") (pinfunction "2_2") (pintype "passive"))
      (node (ref "C25") (pin "2") (pinfunction "2_2") (pintype "passive"))
      (node (ref "C26") (pin "2") (pinfunction "2_2") (pintype "passive"))
      (node (ref "C27") (pin "2") (pinfunction "2_2") (pintype "passive"))
      (node (ref "C3") (pin "2") (pinfunction "2_2") (pintype "passive"))
      (node (ref "C4") (pin "2") (pinfunction "2_2") (pintype "passive"))
      (node (ref "C5") (pin "2") (pinfunction "2_2") (pintype "passive"))
      (node (ref "C6") (pin "2") (pinfunction "2_2") (pintype "passive"))
      (node (ref "C7") (pin "2") (pinfunction "2_2") (pintype "passive"))
      (node (ref "C8") (pin "2") (pinfunction "2_2") (pintype "passive"))
      (node (ref "C9") (pin "2") (pinfunction "2_2") (pintype "passive"))
      (node (ref "D4") (pin "1") (pinfunction "A_1") (pintype "passive"))
      (node (ref "D6") (pin "1") (pinfunction "GND_1") (pintype "bidirectional"))
      (node (ref "D7") (pin "C") (pinfunction "C_C") (pintype "passive"))
      (node (ref "J1") (pin "10") (pinfunction "GND_10") (pintype "bidirectional"))
      (node (ref "J1") (pin "11") (pinfunction "GND_11") (pintype "bidirectional"))
      (node (ref "J1") (pin "12") (pinfunction "GND_12") (pintype "bidirectional"))
      (node (ref "J1") (pin "13") (pinfunction "GND_13") (pintype "bidirectional"))
      (node (ref "J1") (pin "6") (pinfunction "GND_6") (pintype "bidirectional"))
      (node (ref "J2") (pin "2") (pinfunction "2_2") (pintype "passive"))
      (node (ref "J2") (pin "4") (pinfunction "4_4") (pintype "passive"))
      (node (ref "J2") (pin "6") (pinfunction "6_6") (pintype "passive"))
      (node (ref "J3") (pin "1") (pinfunction "1_1") (pintype "power_in"))
      (node (ref "J4") (pin "GND") (pinfunction "GND_GND") (pintype "bidirectional"))
      (node (ref "J4") (pin "GND2") (pinfunction "GND_GND2") (pintype "bidirectional"))
      (node (ref "J6") (pin "1") (pinfunction "1_1") (pintype "power_in"))
      (node (ref "J8") (pin "1") (pinfunction "1_1") (pintype "power_in"))
      (node (ref "J9") (pin "1") (pinfunction "-_1") (pintype "bidirectional"))
      (node (ref "R14") (pin "1") (pinfunction "1_1") (pintype "passive"))
      (node (ref "R17") (pin "2") (pinfunction "2_2") (pintype "passive"))
      (node (ref "R7") (pin "1") (pinfunction "1_1") (pintype "passive"))
      (node (ref "R8") (pin "1") (pinfunction "1_1") (pintype "passive"))
      (node (ref "R9") (pin "1") (pinfunction "1_1") (pintype "passive"))
      (node (ref "S1") (pin "1") (pinfunction "1_1") (pintype "passive"))
      (node (ref "S2") (pin "1") (pinfunction "1_1") (pintype "passive"))
      (node (ref "SHLD") (pin "1") (pinfunction "1_1") (pintype "passive"))
      (node (ref "U1") (pin "1") (pinfunction "GND_1") (pintype "bidirectional"))
      (node (ref "U1") (pin "15") (pinfunction "GND_15") (pintype "bidirectional"))
      (node (ref "U1") (pin "38") (pinfunction "GND_38") (pintype "bidirectional"))
      (node (ref "U1") (pin "GND1") (pinfunction "GND_GND1") (pintype "bidirectional"))
      (node (ref "U1") (pin "GNDT1") (pinfunction "GND_GNDT1") (pintype "bidirectional"))
      (node (ref "U1") (pin "GNDT2") (pinfunction "GND_GNDT2") (pintype "bidirectional"))
      (node (ref "U1") (pin "GNDT3") (pinfunction "GND_GNDT3") (pintype "bidirectional"))
      (node (ref "U1") (pin "GNDT4") (pinfunction "GND_GNDT4") (pintype "bidirectional"))
      (node (ref "U1") (pin "GNDT5") (pinfunction "GND_GNDT5") (pintype "bidirectional"))
      (node (ref "U1") (pin "GNDT6") (pinfunction "GND_GNDT6") (pintype "bidirectional"))
      (node (ref "U1") (pin "GNDT7") (pinfunction "GND_GNDT7") (pintype "bidirectional"))
      (node (ref "U1") (pin "GNDT8") (pinfunction "GND_GNDT8") (pintype "bidirectional"))
      (node (ref "U2") (pin "7") (pinfunction "GND_7") (pintype "bidirectional"))
      (node (ref "U2") (pin "EPAD") (pinfunction "GND_EPAD") (pintype "bidirectional"))
      (node (ref "U3") (pin "2") (pinfunction "GND_2") (pintype "input"))
      (node (ref "U4") (pin "1") (pinfunction "GND_1") (pintype "bidirectional"))
      (node (ref "U5") (pin "2") (pinfunction "VSS_2") (pintype "power_in"))
      (node (ref "U6") (pin "13") (pinfunction "1E_13") (pintype "bidirectional"))
      (node (ref "U6") (pin "6") (pinfunction "3E_6") (pintype "bidirectional"))
      (node (ref "U6") (pin "7") (pinfunction "GND_7") (pintype "bidirectional"))
      (node (ref "U6") (pin "EPAD") (pinfunction "GND_EPAD") (pintype "bidirectional"))
      (node (ref "U7") (pin "1") (pinfunction "CTG_1") (pintype "input"))
      (node (ref "U7") (pin "4") (pinfunction "GND_4") (pintype "bidirectional"))
      (node (ref "U7") (pin "6") (pinfunction "QSTRT_6") (pintype "bidirectional"))
      (node (ref "U7") (pin "9") (pinfunction "GND_9") (pintype "bidirectional"))
      (node (ref "U8") (pin "2") (pinfunction "GND_2") (pintype "input"))
    )
    (net (code "34") (name "Net-(CHG-Pad1)") (class "Default")
      (node (ref "CHG") (pin "1") (pinfunction "1_1") (pintype "passive"))
      (node (ref "D5") (pin "A") (pinfunction "A_A") (pintype "passive"))
    )
    (net (code "35") (name "Net-(D1-PadC)") (class "Default")
      (node (ref "D1") (pin "C") (pinfunction "C_C") (pintype "passive"))
      (node (ref "D2") (pin "C") (pinfunction "C_C") (pintype "passive"))
      (node (ref "D3") (pin "C") (pinfunction "C_C") (pintype "passive"))
      (node (ref "MEAS") (pin "1") (pinfunction "1_1") (pintype "passive"))
      (node (ref "MEAS") (pin "3") (pinfunction "1_3") (pintype "passive"))
    )
    (net (code "36") (name "Net-(D5-PadC)") (class "Default")
      (node (ref "D5") (pin "C") (pinfunction "C_C") (pintype "passive"))
      (node (ref "R13") (pin "1") (pinfunction "1_1") (pintype "passive"))
    )
    (net (code "37") (name "Net-(D6-DI)") (class "Default")
      (node (ref "D6") (pin "3") (pinfunction "DI_3") (pintype "bidirectional"))
      (node (ref "RGB") (pin "1") (pinfunction "1_1") (pintype "passive"))
    )
    (net (code "38") (name "Net-(D6-DO)") (class "Default")
      (node (ref "D6") (pin "4") (pinfunction "DO_4") (pintype "bidirectional"))
      (node (ref "TP1") (pin "1") (pinfunction "1_1") (pintype "bidirectional"))
    )
    (net (code "39") (name "Net-(D7-PadA)") (class "Default")
      (node (ref "D7") (pin "A") (pinfunction "A_A") (pintype "passive"))
      (node (ref "STAT") (pin "1") (pinfunction "1_1") (pintype "passive"))
    )
    (net (code "40") (name "Net-(I2C-Pad1)") (class "Default")
      (node (ref "I2C") (pin "1") (pinfunction "1_1") (pintype "passive"))
      (node (ref "R18") (pin "1") (pinfunction "1_1") (pintype "passive"))
    )
    (net (code "41") (name "Net-(I2C-Pad3)") (class "Default")
      (node (ref "I2C") (pin "3") (pinfunction "3_3") (pintype "passive"))
      (node (ref "R15") (pin "2") (pinfunction "2_2") (pintype "passive"))
    )
    (net (code "42") (name "Net-(J4-CC1)") (class "Default")
      (node (ref "J4") (pin "A5") (pinfunction "CC1_A5") (pintype "bidirectional"))
      (node (ref "R9") (pin "2") (pinfunction "2_2") (pintype "passive"))
    )
    (net (code "43") (name "Net-(J4-CC2)") (class "Default")
      (node (ref "J4") (pin "B5") (pinfunction "CC2_B5") (pintype "bidirectional"))
      (node (ref "R8") (pin "2") (pinfunction "2_2") (pintype "passive"))
    )
    (net (code "44") (name "Net-(J4-SHLD-PadSHLD1)") (class "Default")
      (node (ref "J4") (pin "SHLD1") (pinfunction "SHLD_SHLD1") (pintype "bidirectional"))
      (node (ref "J4") (pin "SHLD2") (pinfunction "SHLD_SHLD2") (pintype "bidirectional"))
      (node (ref "J4") (pin "SHLD3") (pinfunction "SHLD_SHLD3") (pintype "bidirectional"))
      (node (ref "J4") (pin "SHLD4") (pinfunction "SHLD_SHLD4") (pintype "bidirectional"))
      (node (ref "SHLD") (pin "2") (pinfunction "2_2") (pintype "passive"))
    )
    (net (code "45") (name "Net-(Q1A-B)") (class "Default")
      (node (ref "Q1") (pin "5") (pinfunction "B_5") (pintype "passive"))
      (node (ref "R11") (pin "1") (pinfunction "1_1") (pintype "passive"))
    )
    (net (code "46") (name "Net-(Q1B-B)") (class "Default")
      (node (ref "Q1") (pin "2") (pinfunction "B_2") (pintype "passive"))
      (node (ref "R12") (pin "1") (pinfunction "1_1") (pintype "passive"))
    )
    (net (code "47") (name "Net-(R19-Pad1)") (class "Default")
      (node (ref "R19") (pin "1") (pinfunction "1_1") (pintype "passive"))
      (node (ref "STAT") (pin "2") (pinfunction "2_2") (pintype "passive"))
    )
    (net (code "48") (name "Net-(U5-PROG)") (class "Default")
      (node (ref "R14") (pin "2") (pinfunction "2_2") (pintype "passive"))
      (node (ref "U5") (pin "5") (pinfunction "PROG_5") (pintype "input"))
    )
    (net (code "49") (name "Net-(U5-STAT)") (class "Default")
      (node (ref "R13") (pin "2") (pinfunction "2_2") (pintype "passive"))
      (node (ref "TP3") (pin "1") (pinfunction "1_1") (pintype "bidirectional"))
      (node (ref "U5") (pin "1") (pinfunction "STAT_1") (pintype "output"))
    )
    (net (code "50") (name "PWREN") (class "Default")
      (node (ref "R7") (pin "2") (pinfunction "2_2") (pintype "passive"))
      (node (ref "TP4") (pin "1") (pinfunction "1_1") (pintype "bidirectional"))
      (node (ref "U2") (pin "10") (pinfunction "4Z_10") (pintype "bidirectional"))
      (node (ref "U2") (pin "13") (pinfunction "1E_13") (pintype "bidirectional"))
      (node (ref "U2") (pin "5") (pinfunction "2E_5") (pintype "bidirectional"))
      (node (ref "U2") (pin "6") (pinfunction "3E_6") (pintype "bidirectional"))
      (node (ref "U6") (pin "12") (pinfunction "4E_12") (pintype "bidirectional"))
      (node (ref "U6") (pin "5") (pinfunction "2E_5") (pintype "bidirectional"))
      (node (ref "U8") (pin "3") (pinfunction "EN_3") (pintype "input"))
    )
    (net (code "51") (name "QWIIC_SCL") (class "Default")
      (node (ref "J3") (pin "4") (pinfunction "4_4") (pintype "passive"))
      (node (ref "J6") (pin "4") (pinfunction "4_4") (pintype "passive"))
      (node (ref "J8") (pin "4") (pinfunction "4_4") (pintype "passive"))
      (node (ref "U6") (pin "10") (pinfunction "4Z_10") (pintype "bidirectional"))
    )
    (net (code "52") (name "QWIIC_SDA") (class "Default")
      (node (ref "J3") (pin "3") (pinfunction "3_3") (pintype "passive"))
      (node (ref "J6") (pin "3") (pinfunction "3_3") (pintype "passive"))
      (node (ref "J8") (pin "3") (pinfunction "3_3") (pintype "passive"))
      (node (ref "U6") (pin "3") (pinfunction "2Z_3") (pintype "bidirectional"))
    )
    (net (code "53") (name "SD_CMD") (class "Default")
      (node (ref "J1") (pin "3") (pinfunction "CMD/SDI_3") (pintype "bidirectional"))
      (node (ref "R6") (pin "1") (pinfunction "1_1") (pintype "passive"))
      (node (ref "U2") (pin "9") (pinfunction "3Z_9") (pintype "bidirectional"))
    )
    (net (code "54") (name "SD_DAT0") (class "Default")
      (node (ref "J1") (pin "7") (pinfunction "DAT0/SDO_7") (pintype "bidirectional"))
      (node (ref "R5") (pin "1") (pinfunction "1_1") (pintype "passive"))
      (node (ref "U2") (pin "2") (pinfunction "1Z_2") (pintype "bidirectional"))
    )
    (net (code "55") (name "SD_DAT2") (class "Default")
      (node (ref "J1") (pin "1") (pinfunction "DAT2_1") (pintype "bidirectional"))
      (node (ref "R3") (pin "1") (pinfunction "1_1") (pintype "passive"))
      (node (ref "U2") (pin "3") (pinfunction "2Z_3") (pintype "bidirectional"))
    )
    (net (code "56") (name "VIN") (class "Default")
      (node (ref "C10") (pin "1") (pinfunction "1_1") (pintype "passive"))
      (node (ref "C15") (pin "1") (pinfunction "1_1") (pintype "passive"))
      (node (ref "C19") (pin "1") (pinfunction "1_1") (pintype "passive"))
      (node (ref "C21") (pin "1") (pinfunction "1_1") (pintype "passive"))
      (node (ref "C22") (pin "1") (pinfunction "1_1") (pintype "passive"))
      (node (ref "C24") (pin "1") (pinfunction "1_1") (pintype "passive"))
      (node (ref "C9") (pin "1") (pinfunction "1_1") (pintype "passive"))
      (node (ref "CHG") (pin "2") (pinfunction "2_2") (pintype "passive"))
      (node (ref "MEAS") (pin "2") (pinfunction "2_2") (pintype "passive"))
      (node (ref "MEAS") (pin "4") (pinfunction "2_4") (pintype "passive"))
      (node (ref "TP2") (pin "1") (pinfunction "1_1") (pintype "bidirectional"))
      (node (ref "U3") (pin "1") (pinfunction "IN_1") (pintype "input"))
      (node (ref "U3") (pin "3") (pinfunction "EN_3") (pintype "input"))
      (node (ref "U5") (pin "4") (pinfunction "VIN_4") (pintype "power_in"))
      (node (ref "U8") (pin "1") (pinfunction "IN_1") (pintype "input"))
    )
    (net (code "57") (name "V_BATT") (class "Default")
      (node (ref "C16") (pin "1") (pinfunction "1_1") (pintype "passive"))
      (node (ref "C20") (pin "1") (pinfunction "1_1") (pintype "passive"))
      (node (ref "C23") (pin "1") (pinfunction "1_1") (pintype "passive"))
      (node (ref "D1") (pin "A") (pinfunction "A_A") (pintype "passive"))
      (node (ref "J2") (pin "1") (pinfunction "1_1") (pintype "passive"))
      (node (ref "J9") (pin "2") (pinfunction "+_2") (pintype "bidirectional"))
      (node (ref "U5") (pin "3") (pinfunction "VBAT_3") (pintype "power_in"))
      (node (ref "U7") (pin "2") (pinfunction "CELL_2") (pintype "input"))
      (node (ref "U7") (pin "3") (pinfunction "VDD_3") (pintype "bidirectional"))
    )
    (net (code "58") (name "V_USB") (class "Default")
      (node (ref "D2") (pin "A") (pinfunction "A_A") (pintype "passive"))
      (node (ref "D4") (pin "2") (pinfunction "C_2") (pintype "passive"))
      (node (ref "J4") (pin "VBUS1") (pinfunction "VBUS_VBUS1") (pintype "bidirectional"))
      (node (ref "J4") (pin "VBUS2") (pinfunction "VBUS_VBUS2") (pintype "bidirectional"))
    )
    (net (code "59") (name "unconnected-(J1-DET-Pad9)") (class "Default")
      (node (ref "J1") (pin "9") (pinfunction "DET_9") (pintype "bidirectional"))
    )
    (net (code "60") (name "unconnected-(J9-PAD1-PadNC1)") (class "Default")
      (node (ref "J9") (pin "NC1") (pinfunction "PAD1_NC1") (pintype "bidirectional"))
    )
    (net (code "61") (name "unconnected-(J9-PAD2-PadNC2)") (class "Default")
      (node (ref "J9") (pin "NC2") (pinfunction "PAD2_NC2") (pintype "bidirectional"))
    )
    (net (code "62") (name "unconnected-(U1-IA34-Pad6)") (class "Default")
      (node (ref "U1") (pin "6") (pinfunction "IA34_6") (pintype "bidirectional"))
    )
    (net (code "63") (name "unconnected-(U1-IOA27-Pad12)") (class "Default")
      (node (ref "U1") (pin "12") (pinfunction "IOA27_12") (pintype "bidirectional"))
    )
    (net (code "64") (name "unconnected-(U4-R232-Pad15)") (class "Default")
      (node (ref "U4") (pin "15") (pinfunction "R232_15") (pintype "bidirectional"))
    )
    (net (code "65") (name "unconnected-(U4-~{CTS}-Pad9)") (class "Default")
      (node (ref "U4") (pin "9") (pinfunction "~{CTS}_9") (pintype "bidirectional"))
    )
    (net (code "66") (name "unconnected-(U4-~{DCD}-Pad12)") (class "Default")
      (node (ref "U4") (pin "12") (pinfunction "~{DCD}_12") (pintype "bidirectional"))
    )
    (net (code "67") (name "unconnected-(U4-~{DSR}-Pad10)") (class "Default")
      (node (ref "U4") (pin "10") (pinfunction "~{DSR}_10") (pintype "bidirectional"))
    )
    (net (code "68") (name "unconnected-(U4-~{RI}-Pad11)") (class "Default")
      (node (ref "U4") (pin "11") (pinfunction "~{RI}_11") (pintype "bidirectional"))
    )
    (net (code "69") (name "unconnected-(U6-1Y-Pad1)") (class "Default")
      (node (ref "U6") (pin "1") (pinfunction "1Y_1") (pintype "bidirectional"))
    )
    (net (code "70") (name "unconnected-(U6-1Z-Pad2)") (class "Default")
      (node (ref "U6") (pin "2") (pinfunction "1Z_2") (pintype "bidirectional"))
    )
    (net (code "71") (name "unconnected-(U6-3Y-Pad8)") (class "Default")
      (node (ref "U6") (pin "8") (pinfunction "3Y_8") (pintype "bidirectional"))
    )
    (net (code "72") (name "unconnected-(U6-3Z-Pad9)") (class "Default")
      (node (ref "U6") (pin "9") (pinfunction "3Z_9") (pintype "bidirectional"))
    )
    (net (code "73") (name "unconnected-(U7-~{ALRT}-Pad5)") (class "Default")
      (node (ref "U7") (pin "5") (pinfunction "~{ALRT}_5") (pintype "bidirectional"))
    )
  )
)
